# Swagelock_controller_logo.net
KiCad netlist of a schematic drawn in EAGLE
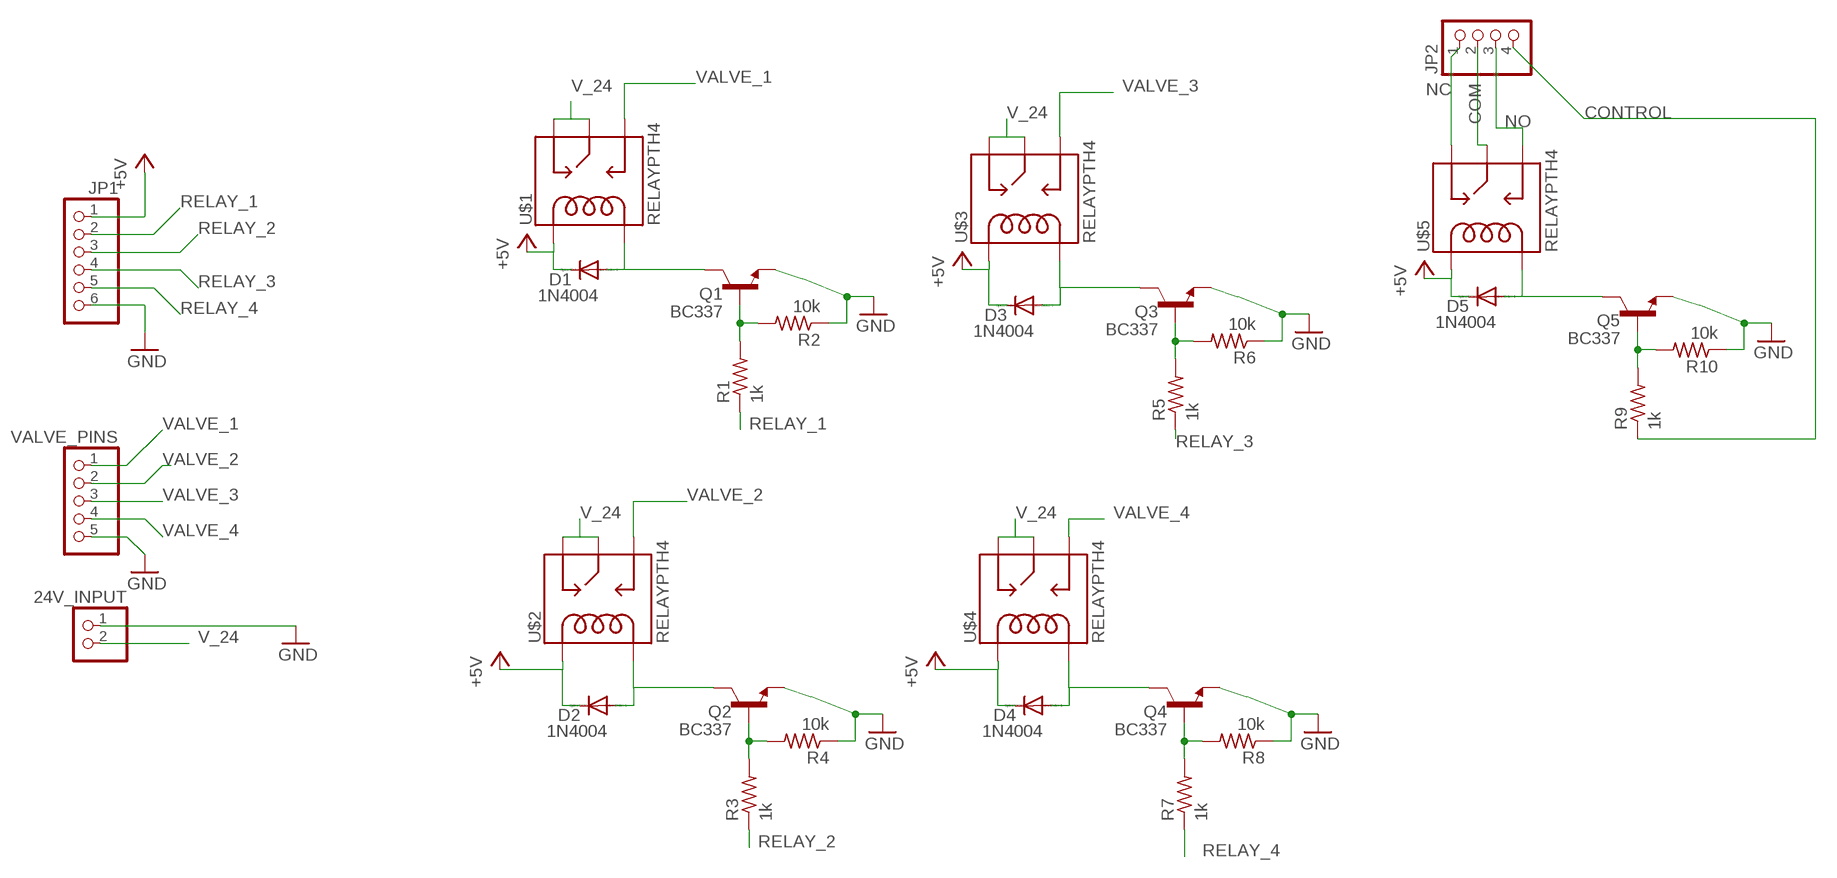
[diagram p0: schematic, sheet 1]

(export (version "E")
  (design (tool "Eeschema 10.0.6"))
  (components
    (comp (ref "24V_INPUT")
      (value "PINHD-1X2")
      (footprint "eagle-import:1X02")
      (libsource (lib "eagle-import") (part "PINHD-1X2"))
    )
    (comp (ref "D1")
      (value "1N4004")
      (footprint "eagle-import:DO41-10")
      (libsource (lib "eagle-import") (part "1N4004"))
    )
    (comp (ref "D2")
      (value "1N4004")
      (footprint "eagle-import:DO41-10")
      (libsource (lib "eagle-import") (part "1N4004"))
    )
    (comp (ref "D3")
      (value "1N4004")
      (footprint "eagle-import:DO41-10")
      (libsource (lib "eagle-import") (part "1N4004"))
    )
    (comp (ref "D4")
      (value "1N4004")
      (footprint "eagle-import:DO41-10")
      (libsource (lib "eagle-import") (part "1N4004"))
    )
    (comp (ref "D5")
      (value "1N4004")
      (footprint "eagle-import:DO41-10")
      (libsource (lib "eagle-import") (part "1N4004"))
    )
    (comp (ref "JP1")
      (value "PINHD-1X6")
      (footprint "eagle-import:1X06")
      (libsource (lib "eagle-import") (part "PINHD-1X6"))
    )
    (comp (ref "JP2")
      (value "PINHD-1X4")
      (footprint "eagle-import:1X04")
      (libsource (lib "eagle-import") (part "PINHD-1X4"))
    )
    (comp (ref "Q1")
      (value "BC337")
      (footprint "eagle-import:TO92")
      (libsource (lib "eagle-import") (part "BC337"))
    )
    (comp (ref "Q2")
      (value "BC337")
      (footprint "eagle-import:TO92")
      (libsource (lib "eagle-import") (part "BC337"))
    )
    (comp (ref "Q3")
      (value "BC337")
      (footprint "eagle-import:TO92")
      (libsource (lib "eagle-import") (part "BC337"))
    )
    (comp (ref "Q4")
      (value "BC337")
      (footprint "eagle-import:TO92")
      (libsource (lib "eagle-import") (part "BC337"))
    )
    (comp (ref "Q5")
      (value "BC337")
      (footprint "eagle-import:TO92")
      (libsource (lib "eagle-import") (part "BC337"))
    )
    (comp (ref "R1")
      (value "1k")
      (footprint "eagle-import:0204_5")
      (libsource (lib "eagle-import") (part "R-US_0204/5"))
    )
    (comp (ref "R2")
      (value "10k")
      (footprint "eagle-import:0204_5")
      (libsource (lib "eagle-import") (part "R-US_0204/5"))
    )
    (comp (ref "R3")
      (value "1k")
      (footprint "eagle-import:0204_5")
      (libsource (lib "eagle-import") (part "R-US_0204/5"))
    )
    (comp (ref "R4")
      (value "10k")
      (footprint "eagle-import:0204_5")
      (libsource (lib "eagle-import") (part "R-US_0204/5"))
    )
    (comp (ref "R5")
      (value "1k")
      (footprint "eagle-import:0204_5")
      (libsource (lib "eagle-import") (part "R-US_0204/5"))
    )
    (comp (ref "R6")
      (value "10k")
      (footprint "eagle-import:0204_5")
      (libsource (lib "eagle-import") (part "R-US_0204/5"))
    )
    (comp (ref "R7")
      (value "1k")
      (footprint "eagle-import:0204_5")
      (libsource (lib "eagle-import") (part "R-US_0204/5"))
    )
    (comp (ref "R8")
      (value "10k")
      (footprint "eagle-import:0204_5")
      (libsource (lib "eagle-import") (part "R-US_0204/5"))
    )
    (comp (ref "R9")
      (value "1k")
      (footprint "eagle-import:0204_5")
      (libsource (lib "eagle-import") (part "R-US_0204/5"))
    )
    (comp (ref "R10")
      (value "10k")
      (footprint "eagle-import:0204_5")
      (libsource (lib "eagle-import") (part "R-US_0204/5"))
    )
    (comp (ref "U$1")
      (value "RELAYPTH4")
      (footprint "eagle-import:RELAY-JZC")
      (libsource (lib "eagle-import") (part "RELAYPTH4"))
    )
    (comp (ref "U$2")
      (value "RELAYPTH4")
      (footprint "eagle-import:RELAY-JZC")
      (libsource (lib "eagle-import") (part "RELAYPTH4"))
    )
    (comp (ref "U$3")
      (value "RELAYPTH4")
      (footprint "eagle-import:RELAY-JZC")
      (libsource (lib "eagle-import") (part "RELAYPTH4"))
    )
    (comp (ref "U$4")
      (value "RELAYPTH4")
      (footprint "eagle-import:RELAY-JZC")
      (libsource (lib "eagle-import") (part "RELAYPTH4"))
    )
    (comp (ref "U$5")
      (value "RELAYPTH4")
      (footprint "eagle-import:RELAY-JZC")
      (libsource (lib "eagle-import") (part "RELAYPTH4"))
    )
    (comp (ref "VALVE_PINS")
      (value "PINHD-1X5")
      (footprint "eagle-import:1X05")
      (libsource (lib "eagle-import") (part "PINHD-1X5"))
    )
  )
  (nets
    (net (code "1") (name "+5V") (class "Default")
      (node (ref "D1") (pin "C") (pinfunction "C_C") (pintype "passive"))
      (node (ref "D2") (pin "C") (pinfunction "C_C") (pintype "passive"))
      (node (ref "D3") (pin "C") (pinfunction "C_C") (pintype "passive"))
      (node (ref "D4") (pin "C") (pinfunction "C_C") (pintype "passive"))
      (node (ref "D5") (pin "C") (pinfunction "C_C") (pintype "passive"))
      (node (ref "JP1") (pin "1") (pinfunction "1_1") (pintype "passive"))
      (node (ref "U$1") (pin "5") (pinfunction "COIL1_5") (pintype "bidirectional"))
      (node (ref "U$2") (pin "5") (pinfunction "COIL1_5") (pintype "bidirectional"))
      (node (ref "U$3") (pin "5") (pinfunction "COIL1_5") (pintype "bidirectional"))
      (node (ref "U$4") (pin "5") (pinfunction "COIL1_5") (pintype "bidirectional"))
      (node (ref "U$5") (pin "5") (pinfunction "COIL1_5") (pintype "bidirectional"))
    )
    (net (code "2") (name "COM") (class "Default")
      (node (ref "JP2") (pin "2") (pinfunction "2_2") (pintype "passive"))
      (node (ref "U$5") (pin "4") (pinfunction "MAIN_4") (pintype "bidirectional"))
    )
    (net (code "3") (name "CONTROL") (class "Default")
      (node (ref "JP2") (pin "4") (pinfunction "4_4") (pintype "passive"))
      (node (ref "R9") (pin "1") (pinfunction "1_1") (pintype "passive"))
    )
    (net (code "4") (name "GND") (class "Default")
      (node (ref "24V_INPUT") (pin "1") (pinfunction "1_1") (pintype "passive"))
      (node (ref "JP1") (pin "6") (pinfunction "6_6") (pintype "passive"))
      (node (ref "Q1") (pin "1") (pinfunction "E_1") (pintype "passive"))
      (node (ref "Q2") (pin "1") (pinfunction "E_1") (pintype "passive"))
      (node (ref "Q3") (pin "1") (pinfunction "E_1") (pintype "passive"))
      (node (ref "Q4") (pin "1") (pinfunction "E_1") (pintype "passive"))
      (node (ref "Q5") (pin "1") (pinfunction "E_1") (pintype "passive"))
      (node (ref "R10") (pin "1") (pinfunction "1_1") (pintype "passive"))
      (node (ref "R2") (pin "1") (pinfunction "1_1") (pintype "passive"))
      (node (ref "R4") (pin "1") (pinfunction "1_1") (pintype "passive"))
      (node (ref "R6") (pin "1") (pinfunction "1_1") (pintype "passive"))
      (node (ref "R8") (pin "1") (pinfunction "1_1") (pintype "passive"))
      (node (ref "VALVE_PINS") (pin "5") (pinfunction "5_5") (pintype "passive"))
    )
    (net (code "5") (name "NC") (class "Default")
      (node (ref "JP2") (pin "1") (pinfunction "1_1") (pintype "passive"))
      (node (ref "U$5") (pin "2") (pinfunction "NC_2") (pintype "bidirectional"))
    )
    (net (code "6") (name "NO") (class "Default")
      (node (ref "JP2") (pin "3") (pinfunction "3_3") (pintype "passive"))
      (node (ref "U$5") (pin "3") (pinfunction "NO_3") (pintype "bidirectional"))
    )
    (net (code "7") (name "Net-(Q1-B)") (class "Default")
      (node (ref "Q1") (pin "2") (pinfunction "B_2") (pintype "passive"))
      (node (ref "R1") (pin "2") (pinfunction "2_2") (pintype "passive"))
      (node (ref "R2") (pin "2") (pinfunction "2_2") (pintype "passive"))
    )
    (net (code "8") (name "Net-(Q1-C)") (class "Default")
      (node (ref "D1") (pin "A") (pinfunction "A_A") (pintype "passive"))
      (node (ref "Q1") (pin "3") (pinfunction "C_3") (pintype "passive"))
      (node (ref "U$1") (pin "1") (pinfunction "COIL2_1") (pintype "bidirectional"))
    )
    (net (code "9") (name "Net-(Q2-B)") (class "Default")
      (node (ref "Q2") (pin "2") (pinfunction "B_2") (pintype "passive"))
      (node (ref "R3") (pin "2") (pinfunction "2_2") (pintype "passive"))
      (node (ref "R4") (pin "2") (pinfunction "2_2") (pintype "passive"))
    )
    (net (code "10") (name "Net-(Q2-C)") (class "Default")
      (node (ref "D2") (pin "A") (pinfunction "A_A") (pintype "passive"))
      (node (ref "Q2") (pin "3") (pinfunction "C_3") (pintype "passive"))
      (node (ref "U$2") (pin "1") (pinfunction "COIL2_1") (pintype "bidirectional"))
    )
    (net (code "11") (name "Net-(Q3-B)") (class "Default")
      (node (ref "Q3") (pin "2") (pinfunction "B_2") (pintype "passive"))
      (node (ref "R5") (pin "2") (pinfunction "2_2") (pintype "passive"))
      (node (ref "R6") (pin "2") (pinfunction "2_2") (pintype "passive"))
    )
    (net (code "12") (name "Net-(Q3-C)") (class "Default")
      (node (ref "D3") (pin "A") (pinfunction "A_A") (pintype "passive"))
      (node (ref "Q3") (pin "3") (pinfunction "C_3") (pintype "passive"))
      (node (ref "U$3") (pin "1") (pinfunction "COIL2_1") (pintype "bidirectional"))
    )
    (net (code "13") (name "Net-(Q4-B)") (class "Default")
      (node (ref "Q4") (pin "2") (pinfunction "B_2") (pintype "passive"))
      (node (ref "R7") (pin "2") (pinfunction "2_2") (pintype "passive"))
      (node (ref "R8") (pin "2") (pinfunction "2_2") (pintype "passive"))
    )
    (net (code "14") (name "Net-(Q4-C)") (class "Default")
      (node (ref "D4") (pin "A") (pinfunction "A_A") (pintype "passive"))
      (node (ref "Q4") (pin "3") (pinfunction "C_3") (pintype "passive"))
      (node (ref "U$4") (pin "1") (pinfunction "COIL2_1") (pintype "bidirectional"))
    )
    (net (code "15") (name "Net-(Q5-B)") (class "Default")
      (node (ref "Q5") (pin "2") (pinfunction "B_2") (pintype "passive"))
      (node (ref "R10") (pin "2") (pinfunction "2_2") (pintype "passive"))
      (node (ref "R9") (pin "2") (pinfunction "2_2") (pintype "passive"))
    )
    (net (code "16") (name "Net-(Q5-C)") (class "Default")
      (node (ref "D5") (pin "A") (pinfunction "A_A") (pintype "passive"))
      (node (ref "Q5") (pin "3") (pinfunction "C_3") (pintype "passive"))
      (node (ref "U$5") (pin "1") (pinfunction "COIL2_1") (pintype "bidirectional"))
    )
    (net (code "17") (name "RELAY_1") (class "Default")
      (node (ref "JP1") (pin "2") (pinfunction "2_2") (pintype "passive"))
      (node (ref "R1") (pin "1") (pinfunction "1_1") (pintype "passive"))
    )
    (net (code "18") (name "RELAY_2") (class "Default")
      (node (ref "JP1") (pin "3") (pinfunction "3_3") (pintype "passive"))
      (node (ref "R3") (pin "1") (pinfunction "1_1") (pintype "passive"))
    )
    (net (code "19") (name "RELAY_3") (class "Default")
      (node (ref "JP1") (pin "4") (pinfunction "4_4") (pintype "passive"))
      (node (ref "R5") (pin "1") (pinfunction "1_1") (pintype "passive"))
    )
    (net (code "20") (name "RELAY_4") (class "Default")
      (node (ref "JP1") (pin "5") (pinfunction "5_5") (pintype "passive"))
      (node (ref "R7") (pin "1") (pinfunction "1_1") (pintype "passive"))
    )
    (net (code "21") (name "VALVE_1") (class "Default")
      (node (ref "U$1") (pin "3") (pinfunction "NO_3") (pintype "bidirectional"))
      (node (ref "VALVE_PINS") (pin "1") (pinfunction "1_1") (pintype "passive"))
    )
    (net (code "22") (name "VALVE_2") (class "Default")
      (node (ref "U$2") (pin "3") (pinfunction "NO_3") (pintype "bidirectional"))
      (node (ref "VALVE_PINS") (pin "2") (pinfunction "2_2") (pintype "passive"))
    )
    (net (code "23") (name "VALVE_3") (class "Default")
      (node (ref "U$3") (pin "3") (pinfunction "NO_3") (pintype "bidirectional"))
      (node (ref "VALVE_PINS") (pin "3") (pinfunction "3_3") (pintype "passive"))
    )
    (net (code "24") (name "VALVE_4") (class "Default")
      (node (ref "U$4") (pin "3") (pinfunction "NO_3") (pintype "bidirectional"))
      (node (ref "VALVE_PINS") (pin "4") (pinfunction "4_4") (pintype "passive"))
    )
    (net (code "25") (name "V_24") (class "Default")
      (node (ref "24V_INPUT") (pin "2") (pinfunction "2_2") (pintype "passive"))
      (node (ref "U$1") (pin "2") (pinfunction "NC_2") (pintype "bidirectional"))
      (node (ref "U$1") (pin "4") (pinfunction "MAIN_4") (pintype "bidirectional"))
      (node (ref "U$2") (pin "2") (pinfunction "NC_2") (pintype "bidirectional"))
      (node (ref "U$2") (pin "4") (pinfunction "MAIN_4") (pintype "bidirectional"))
      (node (ref "U$3") (pin "2") (pinfunction "NC_2") (pintype "bidirectional"))
      (node (ref "U$3") (pin "4") (pinfunction "MAIN_4") (pintype "bidirectional"))
      (node (ref "U$4") (pin "2") (pinfunction "NC_2") (pintype "bidirectional"))
      (node (ref "U$4") (pin "4") (pinfunction "MAIN_4") (pintype "bidirectional"))
    )
  )
)
